# peripherals.net
KiCad netlist of a schematic drawn in Altium Designer
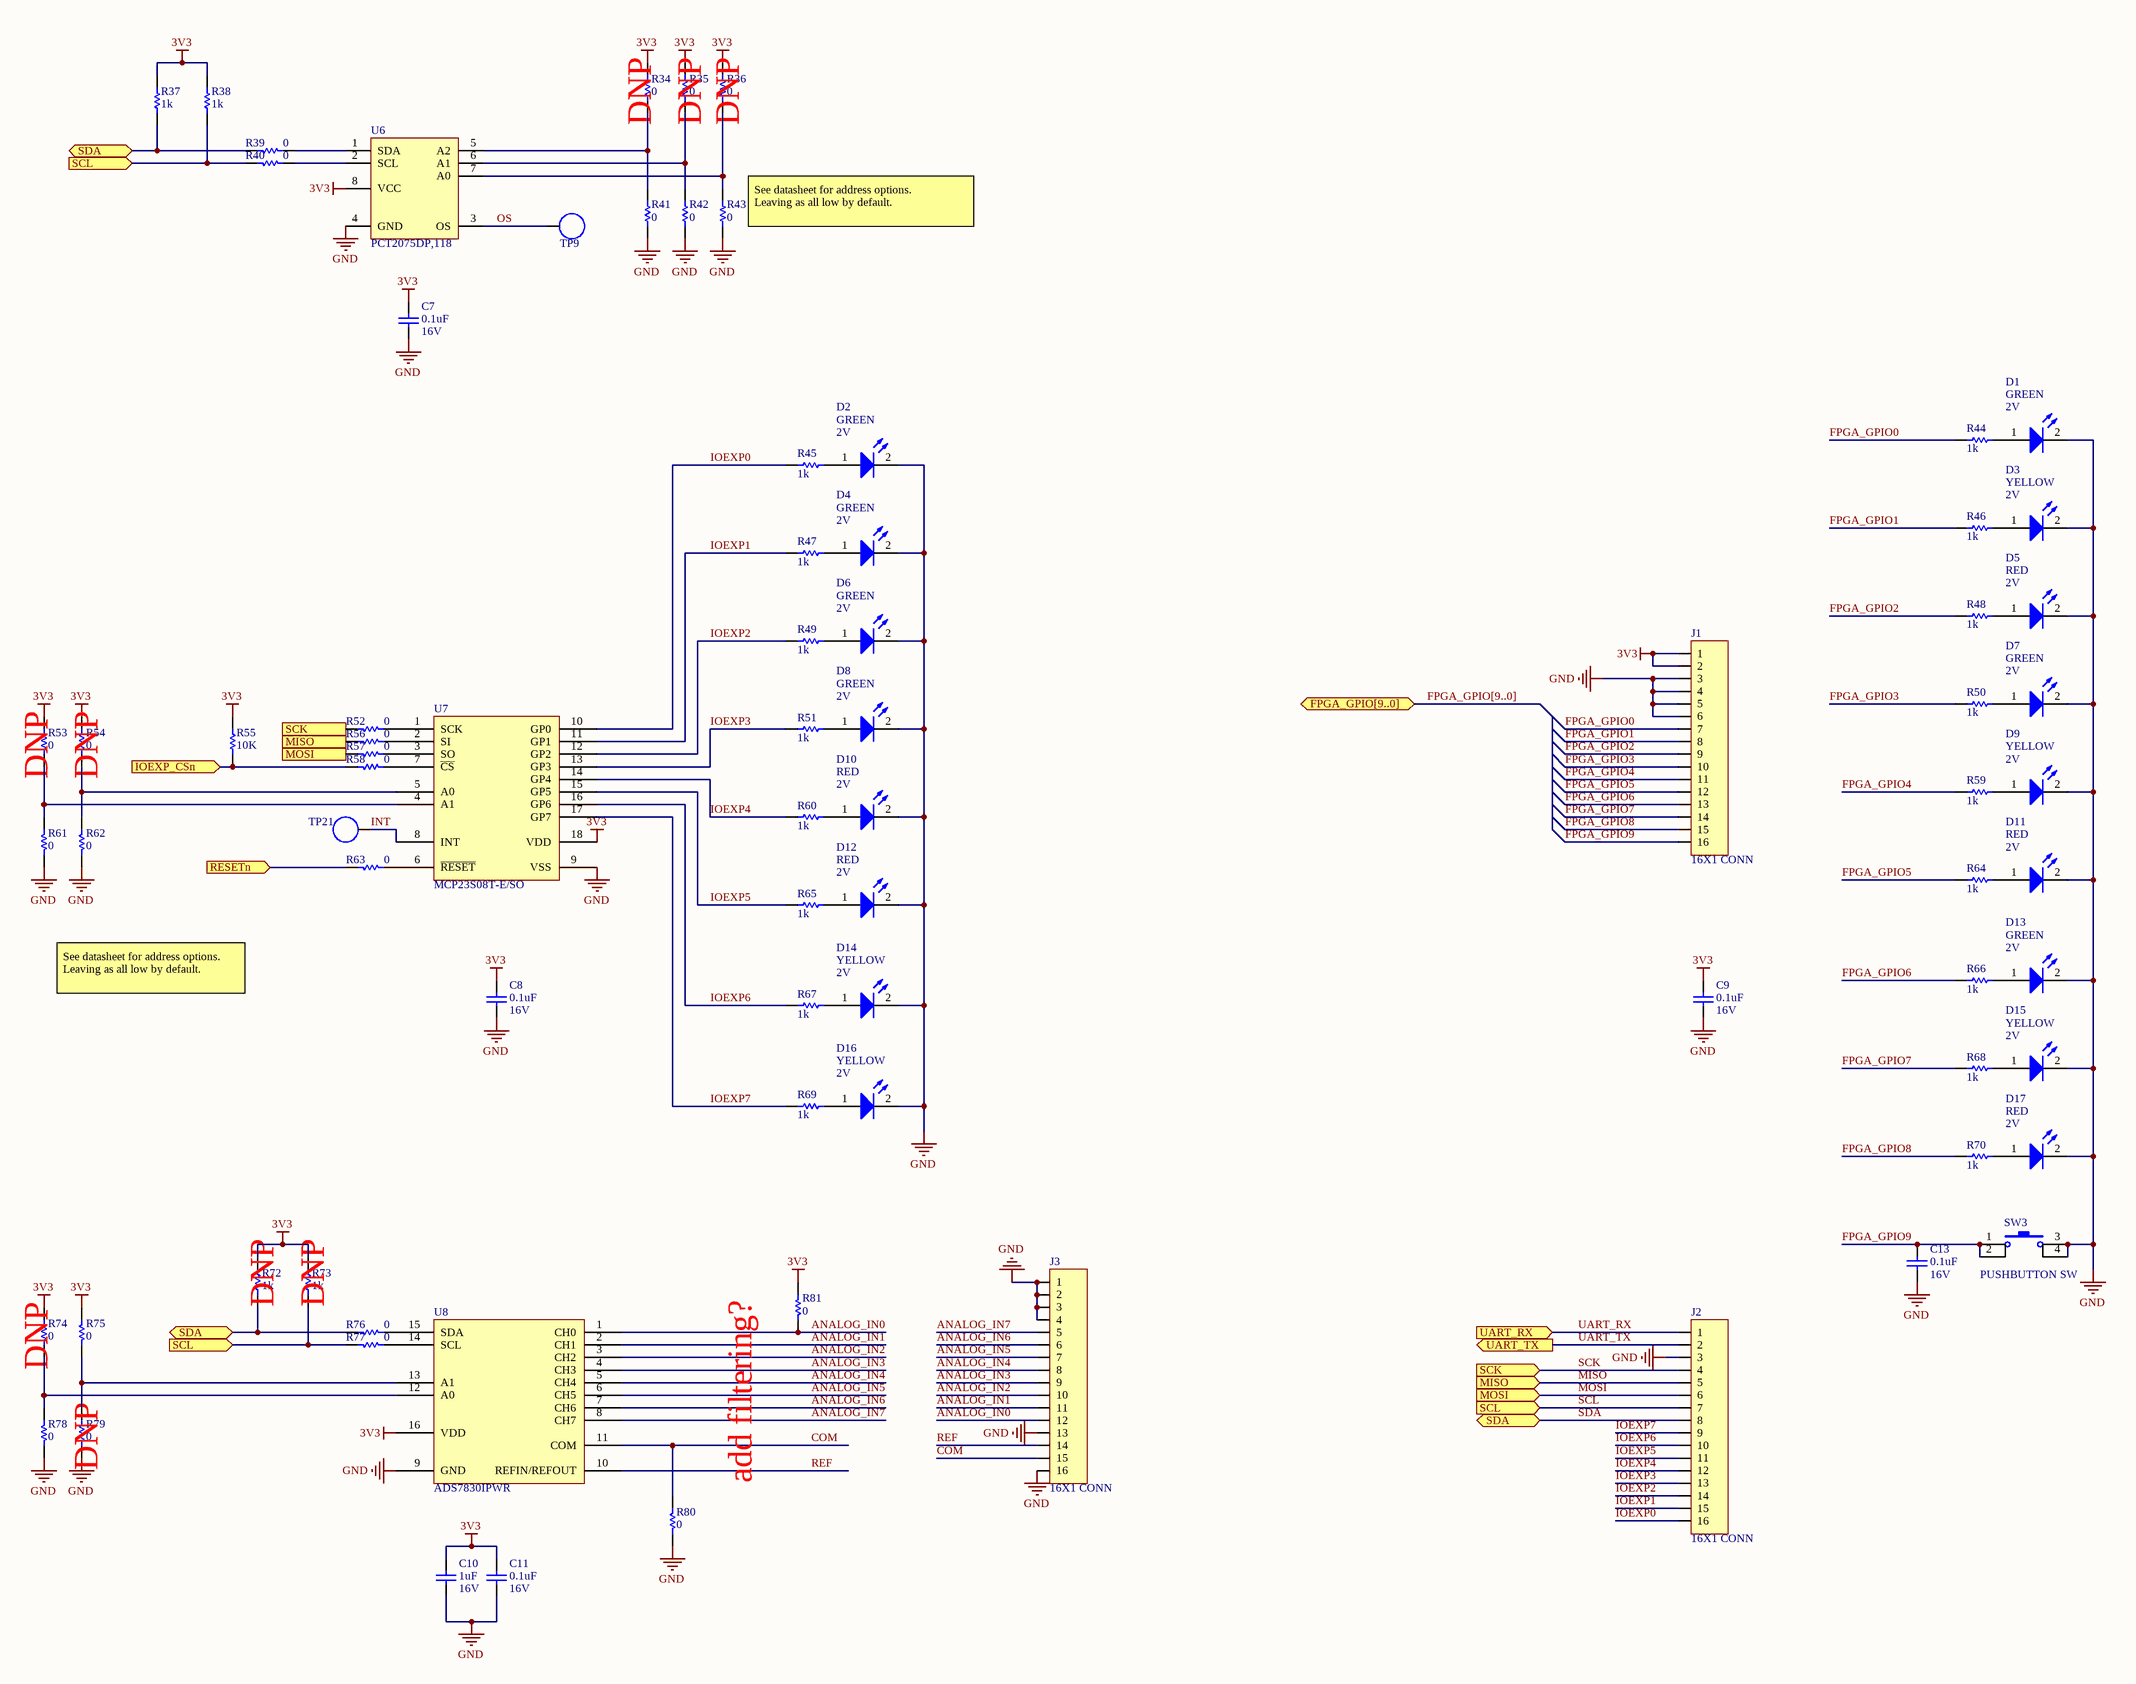
[diagram p0: peripherals.SchDoc]

(export (version "E")
  (design (tool "Eeschema 10.0.6"))
  (components
    (comp (ref "C7")
      (value "Cap_NP")
      (footprint "0805")
      (description "Capacitor")
      (fields
        (field (name "MANUFACTURER") "KEMET")
        (field (name "VOLTAGE") "16V")
        (field (name "CAPACITANCE") "0.1uF")
      )
      (libsource (lib "symbols") (part "Cap_NP"))
    )
    (comp (ref "C8")
      (value "Cap_NP")
      (footprint "0805")
      (description "Capacitor")
      (fields
        (field (name "MANUFACTURER") "KEMET")
        (field (name "VOLTAGE") "16V")
        (field (name "CAPACITANCE") "0.1uF")
      )
      (libsource (lib "symbols") (part "Cap_NP"))
    )
    (comp (ref "C9")
      (value "Cap_NP")
      (footprint "0805")
      (description "Capacitor")
      (fields
        (field (name "MANUFACTURER") "KEMET")
        (field (name "VOLTAGE") "16V")
        (field (name "CAPACITANCE") "0.1uF")
      )
      (libsource (lib "symbols") (part "Cap_NP"))
    )
    (comp (ref "C10")
      (value "Cap_NP")
      (footprint "0805")
      (description "Capacitor")
      (fields
        (field (name "MANUFACTURER") "Taiyo Yuden")
        (field (name "VOLTAGE") "16V")
        (field (name "CAPACITANCE") "1uF")
      )
      (libsource (lib "symbols") (part "Cap_NP"))
    )
    (comp (ref "C11")
      (value "Cap_NP")
      (footprint "0805")
      (description "Capacitor")
      (fields
        (field (name "MANUFACTURER") "KEMET")
        (field (name "VOLTAGE") "16V")
        (field (name "CAPACITANCE") "0.1uF")
      )
      (libsource (lib "symbols") (part "Cap_NP"))
    )
    (comp (ref "C13")
      (value "Cap_NP")
      (footprint "0805")
      (description "Capacitor")
      (fields
        (field (name "MANUFACTURER") "KEMET")
        (field (name "VOLTAGE") "16V")
        (field (name "CAPACITANCE") "0.1uF")
      )
      (libsource (lib "symbols") (part "Cap_NP"))
    )
    (comp (ref "D1")
      (value "LED")
      (footprint "HSMG-C170")
      (fields
        (field (name "MANUFACTURER") "Broadcom")
        (field (name "VF") "2V")
        (field (name "COLOR") "GREEN")
      )
      (libsource (lib "symbols") (part "LED"))
    )
    (comp (ref "D2")
      (value "LED")
      (footprint "HSMG-C170")
      (fields
        (field (name "MANUFACTURER") "Broadcom")
        (field (name "VF") "2V")
        (field (name "COLOR") "GREEN")
      )
      (libsource (lib "symbols") (part "LED"))
    )
    (comp (ref "D3")
      (value "LED")
      (footprint "HSMG-C170")
      (fields
        (field (name "MANUFACTURER") "Broadcom")
        (field (name "VF") "2V")
        (field (name "COLOR") "YELLOW")
      )
      (libsource (lib "symbols") (part "LED"))
    )
    (comp (ref "D4")
      (value "LED")
      (footprint "HSMG-C170")
      (fields
        (field (name "MANUFACTURER") "Broadcom")
        (field (name "VF") "2V")
        (field (name "COLOR") "GREEN")
      )
      (libsource (lib "symbols") (part "LED"))
    )
    (comp (ref "D5")
      (value "LED")
      (footprint "HSMG-C170")
      (fields (field (name "MANUFACTURER") "Broadcom") (field (name "VF") "2V") (field (name "COLOR") "RED"))
      (libsource (lib "symbols") (part "LED"))
    )
    (comp (ref "D6")
      (value "LED")
      (footprint "HSMG-C170")
      (fields
        (field (name "MANUFACTURER") "Broadcom")
        (field (name "VF") "2V")
        (field (name "COLOR") "GREEN")
      )
      (libsource (lib "symbols") (part "LED"))
    )
    (comp (ref "D7")
      (value "LED")
      (footprint "HSMG-C170")
      (fields
        (field (name "MANUFACTURER") "Broadcom")
        (field (name "VF") "2V")
        (field (name "COLOR") "GREEN")
      )
      (libsource (lib "symbols") (part "LED"))
    )
    (comp (ref "D8")
      (value "LED")
      (footprint "HSMG-C170")
      (fields
        (field (name "MANUFACTURER") "Broadcom")
        (field (name "VF") "2V")
        (field (name "COLOR") "GREEN")
      )
      (libsource (lib "symbols") (part "LED"))
    )
    (comp (ref "D9")
      (value "LED")
      (footprint "HSMG-C170")
      (fields
        (field (name "MANUFACTURER") "Broadcom")
        (field (name "VF") "2V")
        (field (name "COLOR") "YELLOW")
      )
      (libsource (lib "symbols") (part "LED"))
    )
    (comp (ref "D10")
      (value "LED")
      (footprint "HSMG-C170")
      (fields (field (name "MANUFACTURER") "Broadcom") (field (name "VF") "2V") (field (name "COLOR") "RED"))
      (libsource (lib "symbols") (part "LED"))
    )
    (comp (ref "D11")
      (value "LED")
      (footprint "HSMG-C170")
      (fields (field (name "MANUFACTURER") "Broadcom") (field (name "VF") "2V") (field (name "COLOR") "RED"))
      (libsource (lib "symbols") (part "LED"))
    )
    (comp (ref "D12")
      (value "LED")
      (footprint "HSMG-C170")
      (fields (field (name "MANUFACTURER") "Broadcom") (field (name "VF") "2V") (field (name "COLOR") "RED"))
      (libsource (lib "symbols") (part "LED"))
    )
    (comp (ref "D13")
      (value "LED")
      (footprint "HSMG-C170")
      (fields
        (field (name "MANUFACTURER") "Broadcom")
        (field (name "VF") "2V")
        (field (name "COLOR") "GREEN")
      )
      (libsource (lib "symbols") (part "LED"))
    )
    (comp (ref "D14")
      (value "LED")
      (footprint "HSMG-C170")
      (fields
        (field (name "MANUFACTURER") "Broadcom")
        (field (name "VF") "2V")
        (field (name "COLOR") "YELLOW")
      )
      (libsource (lib "symbols") (part "LED"))
    )
    (comp (ref "D15")
      (value "LED")
      (footprint "HSMG-C170")
      (fields
        (field (name "MANUFACTURER") "Broadcom")
        (field (name "VF") "2V")
        (field (name "COLOR") "YELLOW")
      )
      (libsource (lib "symbols") (part "LED"))
    )
    (comp (ref "D16")
      (value "LED")
      (footprint "HSMG-C170")
      (fields
        (field (name "MANUFACTURER") "Broadcom")
        (field (name "VF") "2V")
        (field (name "COLOR") "YELLOW")
      )
      (libsource (lib "symbols") (part "LED"))
    )
    (comp (ref "D17")
      (value "LED")
      (footprint "HSMG-C170")
      (fields (field (name "MANUFACTURER") "Broadcom") (field (name "VF") "2V") (field (name "COLOR") "RED"))
      (libsource (lib "symbols") (part "LED"))
    )
    (comp (ref "J1")
      (value "16X1 CONN")
      (footprint "0.100 16X1 HEADER")
      (fields (field (name "MANUFACTURER") "Sullins"))
      (libsource (lib "symbols") (part "16X1 CONN"))
    )
    (comp (ref "J2")
      (value "16X1 CONN")
      (footprint "0.100 16X1 HEADER")
      (fields (field (name "MANUFACTURER") "Sullins"))
      (libsource (lib "symbols") (part "16X1 CONN"))
    )
    (comp (ref "J3")
      (value "16X1 CONN")
      (footprint "0.100 16X1 HEADER")
      (fields (field (name "MANUFACTURER") "Sullins"))
      (libsource (lib "symbols") (part "16X1 CONN"))
    )
    (comp (ref "R34")
      (value "Res")
      (footprint "0805")
      (description "Resistor")
      (fields
        (field (name "MANUFACTURER") "Stackpole Electronics Inc")
        (field (name "TOLERANCE") "Jumper")
        (field (name "RESISTANCE") "0")
      )
      (libsource (lib "symbols") (part "Res"))
    )
    (comp (ref "R35")
      (value "Res")
      (footprint "0805")
      (description "Resistor")
      (fields
        (field (name "MANUFACTURER") "Stackpole Electronics Inc")
        (field (name "TOLERANCE") "Jumper")
        (field (name "RESISTANCE") "0")
      )
      (libsource (lib "symbols") (part "Res"))
    )
    (comp (ref "R36")
      (value "Res")
      (footprint "0805")
      (description "Resistor")
      (fields
        (field (name "MANUFACTURER") "Stackpole Electronics Inc")
        (field (name "TOLERANCE") "Jumper")
        (field (name "RESISTANCE") "0")
      )
      (libsource (lib "symbols") (part "Res"))
    )
    (comp (ref "R37")
      (value "Res")
      (footprint "0805")
      (description "Resistor")
      (fields
        (field (name "MANUFACTURER") "Stackpole Electronics Inc")
        (field (name "TOLERANCE") "5%")
        (field (name "RESISTANCE") "1k")
      )
      (libsource (lib "symbols") (part "Res"))
    )
    (comp (ref "R38")
      (value "Res")
      (footprint "0805")
      (description "Resistor")
      (fields
        (field (name "MANUFACTURER") "Stackpole Electronics Inc")
        (field (name "TOLERANCE") "5%")
        (field (name "RESISTANCE") "1k")
      )
      (libsource (lib "symbols") (part "Res"))
    )
    (comp (ref "R39")
      (value "Res")
      (footprint "0805")
      (description "Resistor")
      (fields
        (field (name "MANUFACTURER") "Stackpole Electronics Inc")
        (field (name "TOLERANCE") "Jumper")
        (field (name "RESISTANCE") "0")
      )
      (libsource (lib "symbols") (part "Res"))
    )
    (comp (ref "R40")
      (value "Res")
      (footprint "0805")
      (description "Resistor")
      (fields
        (field (name "MANUFACTURER") "Stackpole Electronics Inc")
        (field (name "TOLERANCE") "Jumper")
        (field (name "RESISTANCE") "0")
      )
      (libsource (lib "symbols") (part "Res"))
    )
    (comp (ref "R41")
      (value "Res")
      (footprint "0805")
      (description "Resistor")
      (fields
        (field (name "MANUFACTURER") "Stackpole Electronics Inc")
        (field (name "TOLERANCE") "Jumper")
        (field (name "RESISTANCE") "0")
      )
      (libsource (lib "symbols") (part "Res"))
    )
    (comp (ref "R42")
      (value "Res")
      (footprint "0805")
      (description "Resistor")
      (fields
        (field (name "MANUFACTURER") "Stackpole Electronics Inc")
        (field (name "TOLERANCE") "Jumper")
        (field (name "RESISTANCE") "0")
      )
      (libsource (lib "symbols") (part "Res"))
    )
    (comp (ref "R43")
      (value "Res")
      (footprint "0805")
      (description "Resistor")
      (fields
        (field (name "MANUFACTURER") "Stackpole Electronics Inc")
        (field (name "TOLERANCE") "Jumper")
        (field (name "RESISTANCE") "0")
      )
      (libsource (lib "symbols") (part "Res"))
    )
    (comp (ref "R44")
      (value "Res")
      (footprint "0805")
      (description "Resistor")
      (fields
        (field (name "MANUFACTURER") "Stackpole Electronics Inc")
        (field (name "TOLERANCE") "5%")
        (field (name "RESISTANCE") "1k")
      )
      (libsource (lib "symbols") (part "Res"))
    )
    (comp (ref "R45")
      (value "Res")
      (footprint "0805")
      (description "Resistor")
      (fields
        (field (name "MANUFACTURER") "Stackpole Electronics Inc")
        (field (name "TOLERANCE") "5%")
        (field (name "RESISTANCE") "1k")
      )
      (libsource (lib "symbols") (part "Res"))
    )
    (comp (ref "R46")
      (value "Res")
      (footprint "0805")
      (description "Resistor")
      (fields
        (field (name "MANUFACTURER") "Stackpole Electronics Inc")
        (field (name "TOLERANCE") "5%")
        (field (name "RESISTANCE") "1k")
      )
      (libsource (lib "symbols") (part "Res"))
    )
    (comp (ref "R47")
      (value "Res")
      (footprint "0805")
      (description "Resistor")
      (fields
        (field (name "MANUFACTURER") "Stackpole Electronics Inc")
        (field (name "TOLERANCE") "5%")
        (field (name "RESISTANCE") "1k")
      )
      (libsource (lib "symbols") (part "Res"))
    )
    (comp (ref "R48")
      (value "Res")
      (footprint "0805")
      (description "Resistor")
      (fields
        (field (name "MANUFACTURER") "Stackpole Electronics Inc")
        (field (name "TOLERANCE") "5%")
        (field (name "RESISTANCE") "1k")
      )
      (libsource (lib "symbols") (part "Res"))
    )
    (comp (ref "R49")
      (value "Res")
      (footprint "0805")
      (description "Resistor")
      (fields
        (field (name "MANUFACTURER") "Stackpole Electronics Inc")
        (field (name "TOLERANCE") "5%")
        (field (name "RESISTANCE") "1k")
      )
      (libsource (lib "symbols") (part "Res"))
    )
    (comp (ref "R50")
      (value "Res")
      (footprint "0805")
      (description "Resistor")
      (fields
        (field (name "MANUFACTURER") "Stackpole Electronics Inc")
        (field (name "TOLERANCE") "5%")
        (field (name "RESISTANCE") "1k")
      )
      (libsource (lib "symbols") (part "Res"))
    )
    (comp (ref "R51")
      (value "Res")
      (footprint "0805")
      (description "Resistor")
      (fields
        (field (name "MANUFACTURER") "Stackpole Electronics Inc")
        (field (name "TOLERANCE") "5%")
        (field (name "RESISTANCE") "1k")
      )
      (libsource (lib "symbols") (part "Res"))
    )
    (comp (ref "R52")
      (value "Res")
      (footprint "0805")
      (description "Resistor")
      (fields
        (field (name "MANUFACTURER") "Stackpole Electronics Inc")
        (field (name "TOLERANCE") "Jumper")
        (field (name "RESISTANCE") "0")
      )
      (libsource (lib "symbols") (part "Res"))
    )
    (comp (ref "R53")
      (value "Res")
      (footprint "0805")
      (description "Resistor")
      (fields
        (field (name "MANUFACTURER") "Stackpole Electronics Inc")
        (field (name "TOLERANCE") "Jumper")
        (field (name "RESISTANCE") "0")
      )
      (libsource (lib "symbols") (part "Res"))
    )
    (comp (ref "R54")
      (value "Res")
      (footprint "0805")
      (description "Resistor")
      (fields
        (field (name "MANUFACTURER") "Stackpole Electronics Inc")
        (field (name "TOLERANCE") "Jumper")
        (field (name "RESISTANCE") "0")
      )
      (libsource (lib "symbols") (part "Res"))
    )
    (comp (ref "R55")
      (value "Res")
      (footprint "0805")
      (description "Resistor")
      (fields
        (field (name "MANUFACTURER") "Stackpole Electronics Inc")
        (field (name "TOLERANCE") "5%")
        (field (name "RESISTANCE") "10K")
      )
      (libsource (lib "symbols") (part "Res"))
    )
    (comp (ref "R56")
      (value "Res")
      (footprint "0805")
      (description "Resistor")
      (fields
        (field (name "MANUFACTURER") "Stackpole Electronics Inc")
        (field (name "TOLERANCE") "Jumper")
        (field (name "RESISTANCE") "0")
      )
      (libsource (lib "symbols") (part "Res"))
    )
    (comp (ref "R57")
      (value "Res")
      (footprint "0805")
      (description "Resistor")
      (fields
        (field (name "MANUFACTURER") "Stackpole Electronics Inc")
        (field (name "TOLERANCE") "Jumper")
        (field (name "RESISTANCE") "0")
      )
      (libsource (lib "symbols") (part "Res"))
    )
    (comp (ref "R58")
      (value "Res")
      (footprint "0805")
      (description "Resistor")
      (fields
        (field (name "MANUFACTURER") "Stackpole Electronics Inc")
        (field (name "TOLERANCE") "Jumper")
        (field (name "RESISTANCE") "0")
      )
      (libsource (lib "symbols") (part "Res"))
    )
    (comp (ref "R59")
      (value "Res")
      (footprint "0805")
      (description "Resistor")
      (fields
        (field (name "MANUFACTURER") "Stackpole Electronics Inc")
        (field (name "TOLERANCE") "5%")
        (field (name "RESISTANCE") "1k")
      )
      (libsource (lib "symbols") (part "Res"))
    )
    (comp (ref "R60")
      (value "Res")
      (footprint "0805")
      (description "Resistor")
      (fields
        (field (name "MANUFACTURER") "Stackpole Electronics Inc")
        (field (name "TOLERANCE") "5%")
        (field (name "RESISTANCE") "1k")
      )
      (libsource (lib "symbols") (part "Res"))
    )
    (comp (ref "R61")
      (value "Res")
      (footprint "0805")
      (description "Resistor")
      (fields
        (field (name "MANUFACTURER") "Stackpole Electronics Inc")
        (field (name "TOLERANCE") "Jumper")
        (field (name "RESISTANCE") "0")
      )
      (libsource (lib "symbols") (part "Res"))
    )
    (comp (ref "R62")
      (value "Res")
      (footprint "0805")
      (description "Resistor")
      (fields
        (field (name "MANUFACTURER") "Stackpole Electronics Inc")
        (field (name "TOLERANCE") "Jumper")
        (field (name "RESISTANCE") "0")
      )
      (libsource (lib "symbols") (part "Res"))
    )
    (comp (ref "R63")
      (value "Res")
      (footprint "0805")
      (description "Resistor")
      (fields
        (field (name "MANUFACTURER") "Stackpole Electronics Inc")
        (field (name "TOLERANCE") "Jumper")
        (field (name "RESISTANCE") "0")
      )
      (libsource (lib "symbols") (part "Res"))
    )
    (comp (ref "R64")
      (value "Res")
      (footprint "0805")
      (description "Resistor")
      (fields
        (field (name "MANUFACTURER") "Stackpole Electronics Inc")
        (field (name "TOLERANCE") "5%")
        (field (name "RESISTANCE") "1k")
      )
      (libsource (lib "symbols") (part "Res"))
    )
    (comp (ref "R65")
      (value "Res")
      (footprint "0805")
      (description "Resistor")
      (fields
        (field (name "MANUFACTURER") "Stackpole Electronics Inc")
        (field (name "TOLERANCE") "5%")
        (field (name "RESISTANCE") "1k")
      )
      (libsource (lib "symbols") (part "Res"))
    )
    (comp (ref "R66")
      (value "Res")
      (footprint "0805")
      (description "Resistor")
      (fields
        (field (name "MANUFACTURER") "Stackpole Electronics Inc")
        (field (name "TOLERANCE") "5%")
        (field (name "RESISTANCE") "1k")
      )
      (libsource (lib "symbols") (part "Res"))
    )
    (comp (ref "R67")
      (value "Res")
      (footprint "0805")
      (description "Resistor")
      (fields
        (field (name "MANUFACTURER") "Stackpole Electronics Inc")
        (field (name "TOLERANCE") "5%")
        (field (name "RESISTANCE") "1k")
      )
      (libsource (lib "symbols") (part "Res"))
    )
    (comp (ref "R68")
      (value "Res")
      (footprint "0805")
      (description "Resistor")
      (fields
        (field (name "MANUFACTURER") "Stackpole Electronics Inc")
        (field (name "TOLERANCE") "5%")
        (field (name "RESISTANCE") "1k")
      )
      (libsource (lib "symbols") (part "Res"))
    )
    (comp (ref "R69")
      (value "Res")
      (footprint "0805")
      (description "Resistor")
      (fields
        (field (name "MANUFACTURER") "Stackpole Electronics Inc")
        (field (name "TOLERANCE") "5%")
        (field (name "RESISTANCE") "1k")
      )
      (libsource (lib "symbols") (part "Res"))
    )
    (comp (ref "R70")
      (value "Res")
      (footprint "0805")
      (description "Resistor")
      (fields
        (field (name "MANUFACTURER") "Stackpole Electronics Inc")
        (field (name "TOLERANCE") "5%")
        (field (name "RESISTANCE") "1k")
      )
      (libsource (lib "symbols") (part "Res"))
    )
    (comp (ref "R72")
      (value "Res")
      (footprint "0805")
      (description "Resistor")
      (fields
        (field (name "MANUFACTURER") "Stackpole Electronics Inc")
        (field (name "TOLERANCE") "5%")
        (field (name "RESISTANCE") "1k")
      )
      (libsource (lib "symbols") (part "Res"))
    )
    (comp (ref "R73")
      (value "Res")
      (footprint "0805")
      (description "Resistor")
      (fields
        (field (name "MANUFACTURER") "Stackpole Electronics Inc")
        (field (name "TOLERANCE") "5%")
        (field (name "RESISTANCE") "1k")
      )
      (libsource (lib "symbols") (part "Res"))
    )
    (comp (ref "R74")
      (value "Res")
      (footprint "0805")
      (description "Resistor")
      (fields
        (field (name "MANUFACTURER") "Stackpole Electronics Inc")
        (field (name "TOLERANCE") "Jumper")
        (field (name "RESISTANCE") "0")
      )
      (libsource (lib "symbols") (part "Res"))
    )
    (comp (ref "R75")
      (value "Res")
      (footprint "0805")
      (description "Resistor")
      (fields
        (field (name "MANUFACTURER") "Stackpole Electronics Inc")
        (field (name "TOLERANCE") "Jumper")
        (field (name "RESISTANCE") "0")
      )
      (libsource (lib "symbols") (part "Res"))
    )
    (comp (ref "R76")
      (value "Res")
      (footprint "0805")
      (description "Resistor")
      (fields
        (field (name "MANUFACTURER") "Stackpole Electronics Inc")
        (field (name "TOLERANCE") "Jumper")
        (field (name "RESISTANCE") "0")
      )
      (libsource (lib "symbols") (part "Res"))
    )
    (comp (ref "R77")
      (value "Res")
      (footprint "0805")
      (description "Resistor")
      (fields
        (field (name "MANUFACTURER") "Stackpole Electronics Inc")
        (field (name "TOLERANCE") "Jumper")
        (field (name "RESISTANCE") "0")
      )
      (libsource (lib "symbols") (part "Res"))
    )
    (comp (ref "R78")
      (value "Res")
      (footprint "0805")
      (description "Resistor")
      (fields
        (field (name "MANUFACTURER") "Stackpole Electronics Inc")
        (field (name "TOLERANCE") "Jumper")
        (field (name "RESISTANCE") "0")
      )
      (libsource (lib "symbols") (part "Res"))
    )
    (comp (ref "R79")
      (value "Res")
      (footprint "0805")
      (description "Resistor")
      (fields
        (field (name "MANUFACTURER") "Stackpole Electronics Inc")
        (field (name "TOLERANCE") "Jumper")
        (field (name "RESISTANCE") "0")
      )
      (libsource (lib "symbols") (part "Res"))
    )
    (comp (ref "R80")
      (value "Res")
      (footprint "0805")
      (description "Resistor")
      (fields
        (field (name "MANUFACTURER") "Stackpole Electronics Inc")
        (field (name "TOLERANCE") "Jumper")
        (field (name "RESISTANCE") "0")
      )
      (libsource (lib "symbols") (part "Res"))
    )
    (comp (ref "R81")
      (value "Res")
      (footprint "0805")
      (description "Resistor")
      (fields
        (field (name "MANUFACTURER") "Stackpole Electronics Inc")
        (field (name "TOLERANCE") "Jumper")
        (field (name "RESISTANCE") "0")
      )
      (libsource (lib "symbols") (part "Res"))
    )
    (comp (ref "SW3")
      (value "PUSHBUTTON SW")
      (footprint "XKB TS-1187A")
      (fields (field (name "MANUFACTURER") "XKB"))
      (libsource (lib "symbols") (part "SWITCH_PB"))
    )
    (comp (ref "TP9")
      (value "TP")
      (footprint "KEYSTONE_5012")
      (fields (field (name "MANUFACTURER") "Keystone"))
      (libsource (lib "symbols") (part "TP"))
    )
    (comp (ref "TP21")
      (value "TP")
      (footprint "KEYSTONE_5012")
      (fields (field (name "MANUFACTURER") "Keystone"))
      (libsource (lib "symbols") (part "TP"))
    )
    (comp (ref "U6")
      (value "PCT2075DP,118")
      (footprint "NXP TSSOP-8 (SOT505-1)")
      (description "Temperature Sensor Digital, Local -55°C ~ 125°C 11 b 8-TSSOP")
      (fields (field (name "MANUFACTURER") "NXP"))
      (libsource (lib "symbols") (part "PCT2075DP,118"))
    )
    (comp (ref "U7")
      (value "MCP23S08T-E/SO")
      (footprint "MICROCHIP 18-SOIC")
      (fields (field (name "MANUFACTURER") "Microchip"))
      (libsource (lib "symbols") (part "MCP23S08T-E/SO"))
    )
    (comp (ref "U8")
      (value "ADS7830IPWR")
      (footprint "TI PW0016A (16TSSOP)")
      (fields (field (name "MANUFACTURER") "Texas Instruments"))
      (libsource (lib "symbols") (part "ADS7830IPWR"))
    )
  )
  (nets
    (net (code "1") (name "/ANALOG_IN0") (class "Default")
      (node (ref "J3") (pin "12") (pinfunction "12_12") (pintype "passive"))
      (node (ref "R81") (pin "2") (pinfunction "2_2") (pintype "passive"))
      (node (ref "U8") (pin "1") (pinfunction "CH0_1") (pintype "passive"))
    )
    (net (code "2") (name "/ANALOG_IN1") (class "Default")
      (node (ref "J3") (pin "11") (pinfunction "11_11") (pintype "passive"))
      (node (ref "U8") (pin "2") (pinfunction "CH1_2") (pintype "passive"))
    )
    (net (code "3") (name "/ANALOG_IN2") (class "Default")
      (node (ref "J3") (pin "10") (pinfunction "10_10") (pintype "passive"))
      (node (ref "U8") (pin "3") (pinfunction "CH2_3") (pintype "passive"))
    )
    (net (code "4") (name "/ANALOG_IN3") (class "Default")
      (node (ref "J3") (pin "9") (pinfunction "9_9") (pintype "passive"))
      (node (ref "U8") (pin "4") (pinfunction "CH3_4") (pintype "passive"))
    )
    (net (code "5") (name "/ANALOG_IN4") (class "Default")
      (node (ref "J3") (pin "8") (pinfunction "8_8") (pintype "passive"))
      (node (ref "U8") (pin "5") (pinfunction "CH4_5") (pintype "passive"))
    )
    (net (code "6") (name "/ANALOG_IN5") (class "Default")
      (node (ref "J3") (pin "7") (pinfunction "7_7") (pintype "passive"))
      (node (ref "U8") (pin "6") (pinfunction "CH5_6") (pintype "passive"))
    )
    (net (code "7") (name "/ANALOG_IN6") (class "Default")
      (node (ref "J3") (pin "6") (pinfunction "6_6") (pintype "passive"))
      (node (ref "U8") (pin "7") (pinfunction "CH6_7") (pintype "passive"))
    )
    (net (code "8") (name "/ANALOG_IN7") (class "Default")
      (node (ref "J3") (pin "5") (pinfunction "5_5") (pintype "passive"))
      (node (ref "U8") (pin "8") (pinfunction "CH7_8") (pintype "passive"))
    )
    (net (code "9") (name "/COM") (class "Default")
      (node (ref "J3") (pin "15") (pinfunction "15_15") (pintype "passive"))
      (node (ref "R80") (pin "1") (pinfunction "1_1") (pintype "passive"))
      (node (ref "U8") (pin "11") (pinfunction "COM_11") (pintype "passive"))
    )
    (net (code "10") (name "/FPGA_GPIO0") (class "Default")
      (node (ref "J1") (pin "7") (pinfunction "7_7") (pintype "passive"))
      (node (ref "R44") (pin "2") (pinfunction "2_2") (pintype "passive"))
    )
    (net (code "11") (name "/FPGA_GPIO1") (class "Default")
      (node (ref "J1") (pin "8") (pinfunction "8_8") (pintype "passive"))
      (node (ref "R46") (pin "2") (pinfunction "2_2") (pintype "passive"))
    )
    (net (code "12") (name "/FPGA_GPIO2") (class "Default")
      (node (ref "J1") (pin "9") (pinfunction "9_9") (pintype "passive"))
      (node (ref "R48") (pin "2") (pinfunction "2_2") (pintype "passive"))
    )
    (net (code "13") (name "/FPGA_GPIO3") (class "Default")
      (node (ref "J1") (pin "10") (pinfunction "10_10") (pintype "passive"))
      (node (ref "R50") (pin "2") (pinfunction "2_2") (pintype "passive"))
    )
    (net (code "14") (name "/FPGA_GPIO4") (class "Default")
      (node (ref "J1") (pin "11") (pinfunction "11_11") (pintype "passive"))
      (node (ref "R59") (pin "2") (pinfunction "2_2") (pintype "passive"))
    )
    (net (code "15") (name "/FPGA_GPIO5") (class "Default")
      (node (ref "J1") (pin "12") (pinfunction "12_12") (pintype "passive"))
      (node (ref "R64") (pin "2") (pinfunction "2_2") (pintype "passive"))
    )
    (net (code "16") (name "/FPGA_GPIO6") (class "Default")
      (node (ref "J1") (pin "13") (pinfunction "13_13") (pintype "passive"))
      (node (ref "R66") (pin "2") (pinfunction "2_2") (pintype "passive"))
    )
    (net (code "17") (name "/FPGA_GPIO7") (class "Default")
      (node (ref "J1") (pin "14") (pinfunction "14_14") (pintype "passive"))
      (node (ref "R68") (pin "2") (pinfunction "2_2") (pintype "passive"))
    )
    (net (code "18") (name "/FPGA_GPIO8") (class "Default")
      (node (ref "J1") (pin "15") (pinfunction "15_15") (pintype "passive"))
      (node (ref "R70") (pin "2") (pinfunction "2_2") (pintype "passive"))
    )
    (net (code "19") (name "/FPGA_GPIO9") (class "Default")
      (node (ref "C13") (pin "2") (pinfunction "2_2") (pintype "passive"))
      (node (ref "J1") (pin "16") (pinfunction "16_16") (pintype "passive"))
      (node (ref "SW3") (pin "1") (pinfunction "1_1") (pintype "passive"))
      (node (ref "SW3") (pin "2") (pinfunction "2_2") (pintype "passive"))
    )
    (net (code "21") (name "/INT") (class "Default")
      (node (ref "TP21") (pin "1") (pinfunction "1_1") (pintype "passive"))
      (node (ref "U7") (pin "8") (pinfunction "INT_8") (pintype "passive"))
    )
    (net (code "22") (name "/IOEXP0") (class "Default")
      (node (ref "J2") (pin "16") (pinfunction "16_16") (pintype "passive"))
      (node (ref "R45") (pin "2") (pinfunction "2_2") (pintype "passive"))
      (node (ref "U7") (pin "10") (pinfunction "GP0_10") (pintype "passive"))
    )
    (net (code "23") (name "/IOEXP1") (class "Default")
      (node (ref "J2") (pin "15") (pinfunction "15_15") (pintype "passive"))
      (node (ref "R47") (pin "2") (pinfunction "2_2") (pintype "passive"))
      (node (ref "U7") (pin "11") (pinfunction "GP1_11") (pintype "passive"))
    )
    (net (code "24") (name "/IOEXP2") (class "Default")
      (node (ref "J2") (pin "14") (pinfunction "14_14") (pintype "passive"))
      (node (ref "R49") (pin "2") (pinfunction "2_2") (pintype "passive"))
      (node (ref "U7") (pin "12") (pinfunction "GP2_12") (pintype "passive"))
    )
    (net (code "25") (name "/IOEXP3") (class "Default")
      (node (ref "J2") (pin "13") (pinfunction "13_13") (pintype "passive"))
      (node (ref "R51") (pin "2") (pinfunction "2_2") (pintype "passive"))
      (node (ref "U7") (pin "13") (pinfunction "GP3_13") (pintype "passive"))
    )
    (net (code "26") (name "/IOEXP4") (class "Default")
      (node (ref "J2") (pin "12") (pinfunction "12_12") (pintype "passive"))
      (node (ref "R60") (pin "2") (pinfunction "2_2") (pintype "passive"))
      (node (ref "U7") (pin "14") (pinfunction "GP4_14") (pintype "passive"))
    )
    (net (code "27") (name "/IOEXP5") (class "Default")
      (node (ref "J2") (pin "11") (pinfunction "11_11") (pintype "passive"))
      (node (ref "R65") (pin "2") (pinfunction "2_2") (pintype "passive"))
      (node (ref "U7") (pin "15") (pinfunction "GP5_15") (pintype "passive"))
    )
    (net (code "28") (name "/IOEXP6") (class "Default")
      (node (ref "J2") (pin "10") (pinfunction "10_10") (pintype "passive"))
      (node (ref "R67") (pin "2") (pinfunction "2_2") (pintype "passive"))
      (node (ref "U7") (pin "16") (pinfunction "GP6_16") (pintype "passive"))
    )
    (net (code "29") (name "/IOEXP7") (class "Default")
      (node (ref "J2") (pin "9") (pinfunction "9_9") (pintype "passive"))
      (node (ref "R69") (pin "2") (pinfunction "2_2") (pintype "passive"))
      (node (ref "U7") (pin "17") (pinfunction "GP7_17") (pintype "passive"))
    )
    (net (code "30") (name "/IOEXP_CSn") (class "Default")
      (node (ref "R55") (pin "2") (pinfunction "2_2") (pintype "passive"))
      (node (ref "R58") (pin "2") (pinfunction "2_2") (pintype "passive"))
    )
    (net (code "31") (name "/MISO") (class "Default")
      (node (ref "J2") (pin "5") (pinfunction "5_5") (pintype "passive"))
      (node (ref "R56") (pin "2") (pinfunction "2_2") (pintype "passive"))
    )
    (net (code "32") (name "/MOSI") (class "Default")
      (node (ref "J2") (pin "6") (pinfunction "6_6") (pintype "passive"))
      (node (ref "R57") (pin "2") (pinfunction "2_2") (pintype "passive"))
    )
    (net (code "33") (name "/OS") (class "Default")
      (node (ref "TP9") (pin "1") (pinfunction "1_1") (pintype "passive"))
      (node (ref "U6") (pin "3") (pinfunction "OS_3") (pintype "passive"))
    )
    (net (code "34") (name "/REF") (class "Default")
      (node (ref "J3") (pin "14") (pinfunction "14_14") (pintype "passive"))
      (node (ref "U8") (pin "10") (pinfunction "REFIN/REFOUT_10") (pintype "passive"))
    )
    (net (code "35") (name "/RESETn") (class "Default")
      (node (ref "R63") (pin "2") (pinfunction "2_2") (pintype "passive"))
    )
    (net (code "36") (name "/SCK") (class "Default")
      (node (ref "J2") (pin "4") (pinfunction "4_4") (pintype "passive"))
      (node (ref "R52") (pin "2") (pinfunction "2_2") (pintype "passive"))
    )
    (net (code "37") (name "/SCL") (class "Default")
      (node (ref "J2") (pin "7") (pinfunction "7_7") (pintype "passive"))
      (node (ref "R38") (pin "2") (pinfunction "2_2") (pintype "passive"))
      (node (ref "R40") (pin "2") (pinfunction "2_2") (pintype "passive"))
      (node (ref "R73") (pin "2") (pinfunction "2_2") (pintype "passive"))
      (node (ref "R77") (pin "2") (pinfunction "2_2") (pintype "passive"))
    )
    (net (code "38") (name "/SDA") (class "Default")
      (node (ref "J2") (pin "8") (pinfunction "8_8") (pintype "passive"))
      (node (ref "R37") (pin "2") (pinfunction "2_2") (pintype "passive"))
      (node (ref "R39") (pin "2") (pinfunction "2_2") (pintype "passive"))
      (node (ref "R72") (pin "2") (pinfunction "2_2") (pintype "passive"))
      (node (ref "R76") (pin "2") (pinfunction "2_2") (pintype "passive"))
    )
    (net (code "39") (name "/UART_RX") (class "Default")
      (node (ref "J2") (pin "1") (pinfunction "1_1") (pintype "passive"))
    )
    (net (code "40") (name "/UART_TX") (class "Default")
      (node (ref "J2") (pin "2") (pinfunction "2_2") (pintype "passive"))
    )
    (net (code "41") (name "3V3") (class "Default")
      (node (ref "C10") (pin "2") (pinfunction "2_2") (pintype "passive"))
      (node (ref "C11") (pin "2") (pinfunction "2_2") (pintype "passive"))
      (node (ref "C7") (pin "2") (pinfunction "2_2") (pintype "passive"))
      (node (ref "C8") (pin "2") (pinfunction "2_2") (pintype "passive"))
      (node (ref "C9") (pin "2") (pinfunction "2_2") (pintype "passive"))
      (node (ref "J1") (pin "1") (pinfunction "1_1") (pintype "passive"))
      (node (ref "J1") (pin "2") (pinfunction "2_2") (pintype "passive"))
      (node (ref "R34") (pin "1") (pinfunction "1_1") (pintype "passive"))
      (node (ref "R35") (pin "1") (pinfunction "1_1") (pintype "passive"))
      (node (ref "R36") (pin "1") (pinfunction "1_1") (pintype "passive"))
      (node (ref "R37") (pin "1") (pinfunction "1_1") (pintype "passive"))
      (node (ref "R38") (pin "1") (pinfunction "1_1") (pintype "passive"))
      (node (ref "R53") (pin "1") (pinfunction "1_1") (pintype "passive"))
      (node (ref "R54") (pin "1") (pinfunction "1_1") (pintype "passive"))
      (node (ref "R55") (pin "1") (pinfunction "1_1") (pintype "passive"))
      (node (ref "R72") (pin "1") (pinfunction "1_1") (pintype "passive"))
      (node (ref "R73") (pin "1") (pinfunction "1_1") (pintype "passive"))
      (node (ref "R74") (pin "1") (pinfunction "1_1") (pintype "passive"))
      (node (ref "R75") (pin "1") (pinfunction "1_1") (pintype "passive"))
      (node (ref "R81") (pin "1") (pinfunction "1_1") (pintype "passive"))
      (node (ref "U6") (pin "8") (pinfunction "VCC_8") (pintype "passive"))
      (node (ref "U7") (pin "18") (pinfunction "VDD_18") (pintype "passive"))
      (node (ref "U8") (pin "16") (pinfunction "VDD_16") (pintype "passive"))
    )
    (net (code "42") (name "GND") (class "Default")
      (node (ref "C10") (pin "1") (pinfunction "1_1") (pintype "passive"))
      (node (ref "C11") (pin "1") (pinfunction "1_1") (pintype "passive"))
      (node (ref "C13") (pin "1") (pinfunction "1_1") (pintype "passive"))
      (node (ref "C7") (pin "1") (pinfunction "1_1") (pintype "passive"))
      (node (ref "C8") (pin "1") (pinfunction "1_1") (pintype "passive"))
      (node (ref "C9") (pin "1") (pinfunction "1_1") (pintype "passive"))
      (node (ref "D1") (pin "2") (pinfunction "K_2") (pintype "passive"))
      (node (ref "D10") (pin "2") (pinfunction "K_2") (pintype "passive"))
      (node (ref "D11") (pin "2") (pinfunction "K_2") (pintype "passive"))
      (node (ref "D12") (pin "2") (pinfunction "K_2") (pintype "passive"))
      (node (ref "D13") (pin "2") (pinfunction "K_2") (pintype "passive"))
      (node (ref "D14") (pin "2") (pinfunction "K_2") (pintype "passive"))
      (node (ref "D15") (pin "2") (pinfunction "K_2") (pintype "passive"))
      (node (ref "D16") (pin "2") (pinfunction "K_2") (pintype "passive"))
      (node (ref "D17") (pin "2") (pinfunction "K_2") (pintype "passive"))
      (node (ref "D2") (pin "2") (pinfunction "K_2") (pintype "passive"))
      (node (ref "D3") (pin "2") (pinfunction "K_2") (pintype "passive"))
      (node (ref "D4") (pin "2") (pinfunction "K_2") (pintype "passive"))
      (node (ref "D5") (pin "2") (pinfunction "K_2") (pintype "passive"))
      (node (ref "D6") (pin "2") (pinfunction "K_2") (pintype "passive"))
      (node (ref "D7") (pin "2") (pinfunction "K_2") (pintype "passive"))
      (node (ref "D8") (pin "2") (pinfunction "K_2") (pintype "passive"))
      (node (ref "D9") (pin "2") (pinfunction "K_2") (pintype "passive"))
      (node (ref "J1") (pin "3") (pinfunction "3_3") (pintype "passive"))
      (node (ref "J1") (pin "4") (pinfunction "4_4") (pintype "passive"))
      (node (ref "J1") (pin "5") (pinfunction "5_5") (pintype "passive"))
      (node (ref "J1") (pin "6") (pinfunction "6_6") (pintype "passive"))
      (node (ref "J2") (pin "3") (pinfunction "3_3") (pintype "passive"))
      (node (ref "J3") (pin "1") (pinfunction "1_1") (pintype "passive"))
      (node (ref "J3") (pin "13") (pinfunction "13_13") (pintype "passive"))
      (node (ref "J3") (pin "16") (pinfunction "16_16") (pintype "passive"))
      (node (ref "J3") (pin "2") (pinfunction "2_2") (pintype "passive"))
      (node (ref "J3") (pin "3") (pinfunction "3_3") (pintype "passive"))
      (node (ref "J3") (pin "4") (pinfunction "4_4") (pintype "passive"))
      (node (ref "R41") (pin "2") (pinfunction "2_2") (pintype "passive"))
      (node (ref "R42") (pin "2") (pinfunction "2_2") (pintype "passive"))
      (node (ref "R43") (pin "2") (pinfunction "2_2") (pintype "passive"))
      (node (ref "R61") (pin "2") (pinfunction "2_2") (pintype "passive"))
      (node (ref "R62") (pin "2") (pinfunction "2_2") (pintype "passive"))
      (node (ref "R78") (pin "2") (pinfunction "2_2") (pintype "passive"))
      (node (ref "R79") (pin "2") (pinfunction "2_2") (pintype "passive"))
      (node (ref "R80") (pin "2") (pinfunction "2_2") (pintype "passive"))
      (node (ref "SW3") (pin "3") (pinfunction "3_3") (pintype "passive"))
      (node (ref "SW3") (pin "4") (pinfunction "4_4") (pintype "passive"))
      (node (ref "U6") (pin "4") (pinfunction "GND_4") (pintype "passive"))
      (node (ref "U7") (pin "9") (pinfunction "VSS_9") (pintype "passive"))
      (node (ref "U8") (pin "9") (pinfunction "GND_9") (pintype "passive"))
    )
    (net (code "43") (name "Net-(D1-A)") (class "Default")
      (node (ref "D1") (pin "1") (pinfunction "A_1") (pintype "passive"))
      (node (ref "R44") (pin "1") (pinfunction "1_1") (pintype "passive"))
    )
    (net (code "44") (name "Net-(D2-A)") (class "Default")
      (node (ref "D2") (pin "1") (pinfunction "A_1") (pintype "passive"))
      (node (ref "R45") (pin "1") (pinfunction "1_1") (pintype "passive"))
    )
    (net (code "45") (name "Net-(D3-A)") (class "Default")
      (node (ref "D3") (pin "1") (pinfunction "A_1") (pintype "passive"))
      (node (ref "R46") (pin "1") (pinfunction "1_1") (pintype "passive"))
    )
    (net (code "46") (name "Net-(D4-A)") (class "Default")
      (node (ref "D4") (pin "1") (pinfunction "A_1") (pintype "passive"))
      (node (ref "R47") (pin "1") (pinfunction "1_1") (pintype "passive"))
    )
    (net (code "47") (name "Net-(D5-A)") (class "Default")
      (node (ref "D5") (pin "1") (pinfunction "A_1") (pintype "passive"))
      (node (ref "R48") (pin "1") (pinfunction "1_1") (pintype "passive"))
    )
    (net (code "48") (name "Net-(D6-A)") (class "Default")
      (node (ref "D6") (pin "1") (pinfunction "A_1") (pintype "passive"))
      (node (ref "R49") (pin "1") (pinfunction "1_1") (pintype "passive"))
    )
    (net (code "49") (name "Net-(D7-A)") (class "Default")
      (node (ref "D7") (pin "1") (pinfunction "A_1") (pintype "passive"))
      (node (ref "R50") (pin "1") (pinfunction "1_1") (pintype "passive"))
    )
    (net (code "50") (name "Net-(D8-A)") (class "Default")
      (node (ref "D8") (pin "1") (pinfunction "A_1") (pintype "passive"))
      (node (ref "R51") (pin "1") (pinfunction "1_1") (pintype "passive"))
    )
    (net (code "51") (name "Net-(D9-A)") (class "Default")
      (node (ref "D9") (pin "1") (pinfunction "A_1") (pintype "passive"))
      (node (ref "R59") (pin "1") (pinfunction "1_1") (pintype "passive"))
    )
    (net (code "52") (name "Net-(D10-A)") (class "Default")
      (node (ref "D10") (pin "1") (pinfunction "A_1") (pintype "passive"))
      (node (ref "R60") (pin "1") (pinfunction "1_1") (pintype "passive"))
    )
    (net (code "53") (name "Net-(D11-A)") (class "Default")
      (node (ref "D11") (pin "1") (pinfunction "A_1") (pintype "passive"))
      (node (ref "R64") (pin "1") (pinfunction "1_1") (pintype "passive"))
    )
    (net (code "54") (name "Net-(D12-A)") (class "Default")
      (node (ref "D12") (pin "1") (pinfunction "A_1") (pintype "passive"))
      (node (ref "R65") (pin "1") (pinfunction "1_1") (pintype "passive"))
    )
    (net (code "55") (name "Net-(D13-A)") (class "Default")
      (node (ref "D13") (pin "1") (pinfunction "A_1") (pintype "passive"))
      (node (ref "R66") (pin "1") (pinfunction "1_1") (pintype "passive"))
    )
    (net (code "56") (name "Net-(D14-A)") (class "Default")
      (node (ref "D14") (pin "1") (pinfunction "A_1") (pintype "passive"))
      (node (ref "R67") (pin "1") (pinfunction "1_1") (pintype "passive"))
    )
    (net (code "57") (name "Net-(D15-A)") (class "Default")
      (node (ref "D15") (pin "1") (pinfunction "A_1") (pintype "passive"))
      (node (ref "R68") (pin "1") (pinfunction "1_1") (pintype "passive"))
    )
    (net (code "58") (name "Net-(D16-A)") (class "Default")
      (node (ref "D16") (pin "1") (pinfunction "A_1") (pintype "passive"))
      (node (ref "R69") (pin "1") (pinfunction "1_1") (pintype "passive"))
    )
    (net (code "59") (name "Net-(D17-A)") (class "Default")
      (node (ref "D17") (pin "1") (pinfunction "A_1") (pintype "passive"))
      (node (ref "R70") (pin "1") (pinfunction "1_1") (pintype "passive"))
    )
    (net (code "60") (name "Net-(U6-A0)") (class "Default")
      (node (ref "R36") (pin "2") (pinfunction "2_2") (pintype "passive"))
      (node (ref "R43") (pin "1") (pinfunction "1_1") (pintype "passive"))
      (node (ref "U6") (pin "7") (pinfunction "A0_7") (pintype "passive"))
    )
    (net (code "61") (name "Net-(U6-A1)") (class "Default")
      (node (ref "R35") (pin "2") (pinfunction "2_2") (pintype "passive"))
      (node (ref "R42") (pin "1") (pinfunction "1_1") (pintype "passive"))
      (node (ref "U6") (pin "6") (pinfunction "A1_6") (pintype "passive"))
    )
    (net (code "62") (name "Net-(U6-A2)") (class "Default")
      (node (ref "R34") (pin "2") (pinfunction "2_2") (pintype "passive"))
      (node (ref "R41") (pin "1") (pinfunction "1_1") (pintype "passive"))
      (node (ref "U6") (pin "5") (pinfunction "A2_5") (pintype "passive"))
    )
    (net (code "63") (name "Net-(U6-SCL)") (class "Default")
      (node (ref "R40") (pin "1") (pinfunction "1_1") (pintype "passive"))
      (node (ref "U6") (pin "2") (pinfunction "SCL_2") (pintype "passive"))
    )
    (net (code "64") (name "Net-(U6-SDA)") (class "Default")
      (node (ref "R39") (pin "1") (pinfunction "1_1") (pintype "passive"))
      (node (ref "U6") (pin "1") (pinfunction "SDA_1") (pintype "passive"))
    )
    (net (code "65") (name "Net-(U7-A0)") (class "Default")
      (node (ref "R54") (pin "2") (pinfunction "2_2") (pintype "passive"))
      (node (ref "R62") (pin "1") (pinfunction "1_1") (pintype "passive"))
      (node (ref "U7") (pin "5") (pinfunction "A0_5") (pintype "passive"))
    )
    (net (code "66") (name "Net-(U7-A1)") (class "Default")
      (node (ref "R53") (pin "2") (pinfunction "2_2") (pintype "passive"))
      (node (ref "R61") (pin "1") (pinfunction "1_1") (pintype "passive"))
      (node (ref "U7") (pin "4") (pinfunction "A1_4") (pintype "passive"))
    )
    (net (code "67") (name "Net-(U7-SCK)") (class "Default")
      (node (ref "R52") (pin "1") (pinfunction "1_1") (pintype "passive"))
      (node (ref "U7") (pin "1") (pinfunction "SCK_1") (pintype "passive"))
    )
    (net (code "68") (name "Net-(U7-SI)") (class "Default")
      (node (ref "R56") (pin "1") (pinfunction "1_1") (pintype "passive"))
      (node (ref "U7") (pin "2") (pinfunction "SI_2") (pintype "passive"))
    )
    (net (code "69") (name "Net-(U7-SO)") (class "Default")
      (node (ref "R57") (pin "1") (pinfunction "1_1") (pintype "passive"))
      (node (ref "U7") (pin "3") (pinfunction "SO_3") (pintype "passive"))
    )
    (net (code "70") (name "Net-(U7-~{CS})") (class "Default")
      (node (ref "R58") (pin "1") (pinfunction "1_1") (pintype "passive"))
      (node (ref "U7") (pin "7") (pinfunction "~{CS}_7") (pintype "passive"))
    )
    (net (code "71") (name "Net-(U7-~{RESET})") (class "Default")
      (node (ref "R63") (pin "1") (pinfunction "1_1") (pintype "passive"))
      (node (ref "U7") (pin "6") (pinfunction "~{RESET}_6") (pintype "passive"))
    )
    (net (code "72") (name "Net-(U8-A0)") (class "Default")
      (node (ref "R74") (pin "2") (pinfunction "2_2") (pintype "passive"))
      (node (ref "R78") (pin "1") (pinfunction "1_1") (pintype "passive"))
      (node (ref "U8") (pin "12") (pinfunction "A0_12") (pintype "passive"))
    )
    (net (code "73") (name "Net-(U8-A1)") (class "Default")
      (node (ref "R75") (pin "2") (pinfunction "2_2") (pintype "passive"))
      (node (ref "R79") (pin "1") (pinfunction "1_1") (pintype "passive"))
      (node (ref "U8") (pin "13") (pinfunction "A1_13") (pintype "passive"))
    )
    (net (code "74") (name "Net-(U8-SCL)") (class "Default")
      (node (ref "R77") (pin "1") (pinfunction "1_1") (pintype "passive"))
      (node (ref "U8") (pin "14") (pinfunction "SCL_14") (pintype "passive"))
    )
    (net (code "75") (name "Net-(U8-SDA)") (class "Default")
      (node (ref "R76") (pin "1") (pinfunction "1_1") (pintype "passive"))
      (node (ref "U8") (pin "15") (pinfunction "SDA_15") (pintype "passive"))
    )
  )
)
